# ws2811.net
KiCad netlist of a schematic drawn in EAGLE
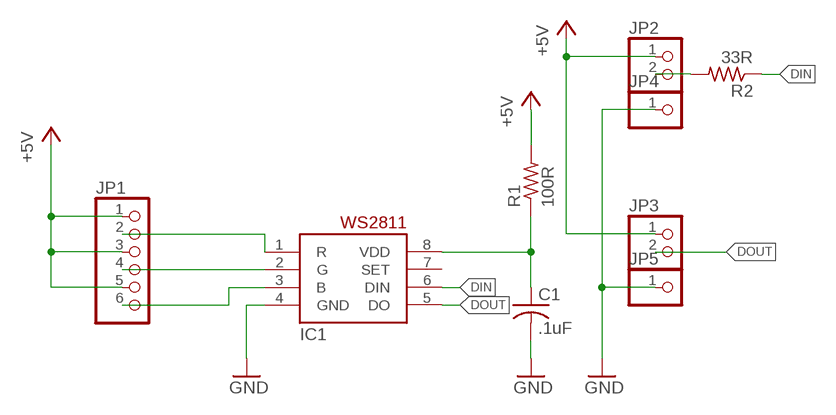
[diagram p0: schematic, sheet 1]

(export (version "E")
  (design (tool "Eeschema 10.0.6"))
  (components
    (comp (ref "C1")
      (value ".1uF")
      (footprint "eagle-import:C0402")
      (libsource (lib "eagle-import") (part "C-USC0402"))
    )
    (comp (ref "IC1")
      (value "WS2811-SOP8")
      (footprint "eagle-import:SO08-SKINNYPADS")
      (libsource (lib "eagle-import") (part "WS2811-SOP8"))
    )
    (comp (ref "JP1")
      (value "PINHD-1X6")
      (footprint "eagle-import:1X06")
      (libsource (lib "eagle-import") (part "PINHD-1X6"))
    )
    (comp (ref "JP2")
      (value "PINHD-1X2")
      (footprint "eagle-import:1X02")
      (libsource (lib "eagle-import") (part "PINHD-1X2"))
    )
    (comp (ref "JP3")
      (value "PINHD-1X2")
      (footprint "eagle-import:1X02")
      (libsource (lib "eagle-import") (part "PINHD-1X2"))
    )
    (comp (ref "JP4")
      (value "PINHD-1X1")
      (footprint "eagle-import:1X01")
      (libsource (lib "eagle-import") (part "PINHD-1X1"))
    )
    (comp (ref "JP5")
      (value "PINHD-1X1")
      (footprint "eagle-import:1X01")
      (libsource (lib "eagle-import") (part "PINHD-1X1"))
    )
    (comp (ref "R1")
      (value "100R")
      (footprint "eagle-import:R0402")
      (libsource (lib "eagle-import") (part "R-US_R0402"))
    )
    (comp (ref "R2")
      (value "33R")
      (footprint "eagle-import:R0402")
      (libsource (lib "eagle-import") (part "R-US_R0402"))
    )
  )
  (nets
    (net (code "1") (name "+5V") (class "Default")
      (node (ref "JP1") (pin "1") (pinfunction "1_1") (pintype "passive"))
      (node (ref "JP1") (pin "3") (pinfunction "3_3") (pintype "passive"))
      (node (ref "JP1") (pin "5") (pinfunction "5_5") (pintype "passive"))
      (node (ref "JP2") (pin "1") (pinfunction "1_1") (pintype "passive"))
      (node (ref "JP3") (pin "1") (pinfunction "1_1") (pintype "passive"))
      (node (ref "R1") (pin "2") (pinfunction "2_2") (pintype "passive"))
    )
    (net (code "2") (name "DIN") (class "Default")
      (node (ref "IC1") (pin "6") (pinfunction "DIN_6") (pintype "input"))
      (node (ref "R2") (pin "1") (pinfunction "1_1") (pintype "passive"))
    )
    (net (code "3") (name "DOUT") (class "Default")
      (node (ref "IC1") (pin "5") (pinfunction "DO_5") (pintype "output"))
      (node (ref "JP3") (pin "2") (pinfunction "2_2") (pintype "passive"))
    )
    (net (code "4") (name "GND") (class "Default")
      (node (ref "C1") (pin "2") (pinfunction "2_2") (pintype "passive"))
      (node (ref "IC1") (pin "4") (pinfunction "GND_4") (pintype "power_in"))
      (node (ref "JP4") (pin "1") (pinfunction "1_1") (pintype "passive"))
      (node (ref "JP5") (pin "1") (pinfunction "1_1") (pintype "passive"))
    )
    (net (code "5") (name "Net-(IC1-B)") (class "Default")
      (node (ref "IC1") (pin "3") (pinfunction "B_3") (pintype "open_collector"))
      (node (ref "JP1") (pin "6") (pinfunction "6_6") (pintype "passive"))
    )
    (net (code "6") (name "Net-(IC1-G)") (class "Default")
      (node (ref "IC1") (pin "2") (pinfunction "G_2") (pintype "open_collector"))
      (node (ref "JP1") (pin "4") (pinfunction "4_4") (pintype "passive"))
    )
    (net (code "7") (name "Net-(IC1-R)") (class "Default")
      (node (ref "IC1") (pin "1") (pinfunction "R_1") (pintype "open_collector"))
      (node (ref "JP1") (pin "2") (pinfunction "2_2") (pintype "passive"))
    )
    (net (code "8") (name "Net-(IC1-VDD)") (class "Default")
      (node (ref "C1") (pin "1") (pinfunction "1_1") (pintype "passive"))
      (node (ref "IC1") (pin "8") (pinfunction "VDD_8") (pintype "power_in"))
      (node (ref "R1") (pin "1") (pinfunction "1_1") (pintype "passive"))
    )
    (net (code "9") (name "Net-(JP2-Pad2)") (class "Default")
      (node (ref "JP2") (pin "2") (pinfunction "2_2") (pintype "passive"))
      (node (ref "R2") (pin "2") (pinfunction "2_2") (pintype "passive"))
    )
    (net (code "10") (name "unconnected-(IC1-SET-Pad7)") (class "Default")
      (node (ref "IC1") (pin "7") (pinfunction "SET_7") (pintype "input"))
    )
  )
)
